# LinearMixer.net
KiCad netlist of a schematic drawn in EAGLE
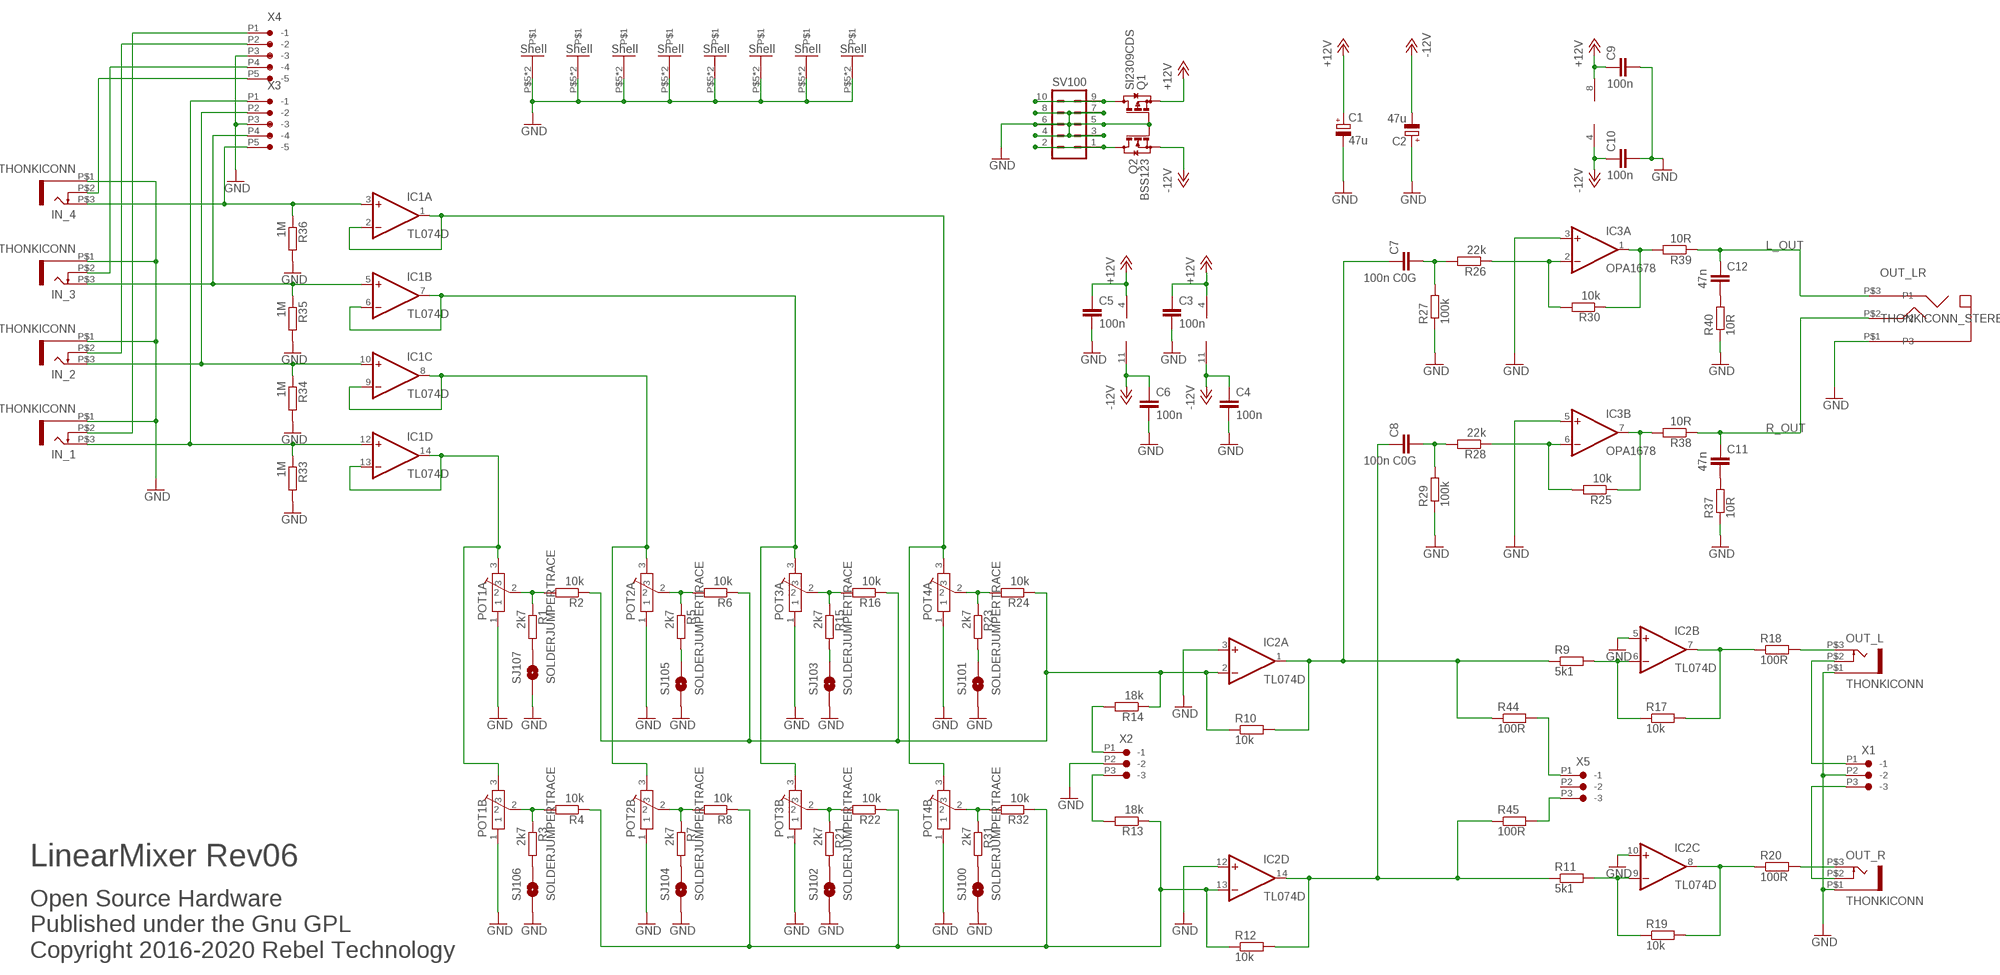
[diagram p0: schematic, sheet 1]

(export (version "E")
  (design (tool "Eeschema 10.0.6"))
  (components
    (comp (ref "C1")
      (value "47u")
      (footprint "eagle-import:153CLV-0505")
      (libsource (lib "eagle-import") (part "CPOL-EU153CLV-0505"))
    )
    (comp (ref "C2")
      (value "47u")
      (footprint "eagle-import:153CLV-0505")
      (libsource (lib "eagle-import") (part "CPOL-EU153CLV-0505"))
    )
    (comp (ref "C3")
      (value "100n")
      (footprint "eagle-import:C0603")
      (libsource (lib "eagle-import") (part "Rebel_15457297_C-EUC0603"))
    )
    (comp (ref "C4")
      (value "100n")
      (footprint "eagle-import:C0603")
      (libsource (lib "eagle-import") (part "Rebel_15457297_C-EUC0603"))
    )
    (comp (ref "C5")
      (value "100n")
      (footprint "eagle-import:C0603")
      (libsource (lib "eagle-import") (part "Rebel_15457297_C-EUC0603"))
    )
    (comp (ref "C6")
      (value "100n")
      (footprint "eagle-import:C0603")
      (libsource (lib "eagle-import") (part "Rebel_15457297_C-EUC0603"))
    )
    (comp (ref "C7")
      (value "100n C0G")
      (footprint "eagle-import:C1210")
      (libsource (lib "eagle-import") (part "C-EUC1210"))
    )
    (comp (ref "C8")
      (value "100n C0G")
      (footprint "eagle-import:C1210")
      (libsource (lib "eagle-import") (part "C-EUC1210"))
    )
    (comp (ref "C9")
      (value "100n")
      (footprint "eagle-import:C0603")
      (libsource (lib "eagle-import") (part "Rebel_15457297_C-EUC0603"))
    )
    (comp (ref "C10")
      (value "100n")
      (footprint "eagle-import:C0603")
      (libsource (lib "eagle-import") (part "Rebel_15457297_C-EUC0603"))
    )
    (comp (ref "C11")
      (value "47n")
      (footprint "eagle-import:C0603")
      (libsource (lib "eagle-import") (part "Rebel_15457297_C-EUC0603"))
    )
    (comp (ref "C12")
      (value "47n")
      (footprint "eagle-import:C0603")
      (libsource (lib "eagle-import") (part "Rebel_15457297_C-EUC0603"))
    )
    (comp (ref "IC1")
      (value "TL074D")
      (footprint "eagle-import:SO14")
      (libsource (lib "eagle-import") (part "TL074D"))
    )
    (comp (ref "IC2")
      (value "TL074D")
      (footprint "eagle-import:SO14")
      (libsource (lib "eagle-import") (part "TL074D"))
    )
    (comp (ref "IC3")
      (value "OPA1678")
      (footprint "eagle-import:SO08")
      (libsource (lib "eagle-import") (part "NE5532D"))
    )
    (comp (ref "IN_1")
      (value "THONKICONN")
      (footprint "eagle-import:THONKICONN")
      (libsource (lib "eagle-import") (part "THONKICONN"))
    )
    (comp (ref "IN_2")
      (value "THONKICONN")
      (footprint "eagle-import:THONKICONN")
      (libsource (lib "eagle-import") (part "THONKICONN"))
    )
    (comp (ref "IN_3")
      (value "THONKICONN")
      (footprint "eagle-import:THONKICONN")
      (libsource (lib "eagle-import") (part "THONKICONN"))
    )
    (comp (ref "IN_4")
      (value "THONKICONN")
      (footprint "eagle-import:THONKICONN")
      (libsource (lib "eagle-import") (part "THONKICONN"))
    )
    (comp (ref "OUT_L")
      (value "THONKICONN")
      (footprint "eagle-import:THONKICONN")
      (libsource (lib "eagle-import") (part "THONKICONN"))
    )
    (comp (ref "OUT_LR")
      (value "THONKICONN_STEREO")
      (footprint "eagle-import:THONKICONN_STEREO")
      (libsource (lib "eagle-import") (part "THONKICONN_STEREO"))
    )
    (comp (ref "OUT_R")
      (value "THONKICONN")
      (footprint "eagle-import:THONKICONN")
      (libsource (lib "eagle-import") (part "THONKICONN"))
    )
    (comp (ref "POT1A")
      (value "POT-ALPS-RK09L1140")
      (footprint "eagle-import:POT-ALPS-RK09L1140")
      (libsource (lib "eagle-import") (part "POT-ALPS-RK09L1140"))
    )
    (comp (ref "POT1B")
      (value "POT-ALPS-RK09L1140")
      (footprint "eagle-import:POT-ALPS-RK09L1140")
      (libsource (lib "eagle-import") (part "POT-ALPS-RK09L1140"))
    )
    (comp (ref "POT2A")
      (value "POT-ALPS-RK09L1140")
      (footprint "eagle-import:POT-ALPS-RK09L1140")
      (libsource (lib "eagle-import") (part "POT-ALPS-RK09L1140"))
    )
    (comp (ref "POT2B")
      (value "POT-ALPS-RK09L1140")
      (footprint "eagle-import:POT-ALPS-RK09L1140")
      (libsource (lib "eagle-import") (part "POT-ALPS-RK09L1140"))
    )
    (comp (ref "POT3A")
      (value "POT-ALPS-RK09L1140")
      (footprint "eagle-import:POT-ALPS-RK09L1140")
      (libsource (lib "eagle-import") (part "POT-ALPS-RK09L1140"))
    )
    (comp (ref "POT3B")
      (value "POT-ALPS-RK09L1140")
      (footprint "eagle-import:POT-ALPS-RK09L1140")
      (libsource (lib "eagle-import") (part "POT-ALPS-RK09L1140"))
    )
    (comp (ref "POT4A")
      (value "POT-ALPS-RK09L1140")
      (footprint "eagle-import:POT-ALPS-RK09L1140")
      (libsource (lib "eagle-import") (part "POT-ALPS-RK09L1140"))
    )
    (comp (ref "POT4B")
      (value "POT-ALPS-RK09L1140")
      (footprint "eagle-import:POT-ALPS-RK09L1140")
      (libsource (lib "eagle-import") (part "POT-ALPS-RK09L1140"))
    )
    (comp (ref "Q1")
      (value "SI2309CDS")
      (footprint "eagle-import:SOT23")
      (libsource (lib "eagle-import") (part "BSS84"))
    )
    (comp (ref "Q2")
      (value "BSS123")
      (footprint "eagle-import:SOT23")
      (libsource (lib "eagle-import") (part "BSS123"))
    )
    (comp (ref "R1")
      (value "2k7")
      (footprint "eagle-import:0603")
      (libsource (lib "eagle-import") (part "Rebel_15457297_R-EU_0603"))
    )
    (comp (ref "R2")
      (value "10k")
      (footprint "eagle-import:0603")
      (libsource (lib "eagle-import") (part "Rebel_15457297_R-EU_0603"))
    )
    (comp (ref "R3")
      (value "2k7")
      (footprint "eagle-import:0603")
      (libsource (lib "eagle-import") (part "Rebel_15457297_R-EU_0603"))
    )
    (comp (ref "R4")
      (value "10k")
      (footprint "eagle-import:0603")
      (libsource (lib "eagle-import") (part "Rebel_15457297_R-EU_0603"))
    )
    (comp (ref "R5")
      (value "2k7")
      (footprint "eagle-import:0603")
      (libsource (lib "eagle-import") (part "Rebel_15457297_R-EU_0603"))
    )
    (comp (ref "R6")
      (value "10k")
      (footprint "eagle-import:0603")
      (libsource (lib "eagle-import") (part "Rebel_15457297_R-EU_0603"))
    )
    (comp (ref "R7")
      (value "2k7")
      (footprint "eagle-import:0603")
      (libsource (lib "eagle-import") (part "Rebel_15457297_R-EU_0603"))
    )
    (comp (ref "R8")
      (value "10k")
      (footprint "eagle-import:0603")
      (libsource (lib "eagle-import") (part "Rebel_15457297_R-EU_0603"))
    )
    (comp (ref "R9")
      (value "5k1")
      (footprint "eagle-import:0603")
      (libsource (lib "eagle-import") (part "Rebel_15457297_R-EU_0603"))
    )
    (comp (ref "R10")
      (value "10k")
      (footprint "eagle-import:0603")
      (libsource (lib "eagle-import") (part "Rebel_15457297_R-EU_0603"))
    )
    (comp (ref "R11")
      (value "5k1")
      (footprint "eagle-import:0603")
      (libsource (lib "eagle-import") (part "Rebel_15457297_R-EU_0603"))
    )
    (comp (ref "R12")
      (value "10k")
      (footprint "eagle-import:0603")
      (libsource (lib "eagle-import") (part "Rebel_15457297_R-EU_0603"))
    )
    (comp (ref "R13")
      (value "18k")
      (footprint "eagle-import:0603")
      (libsource (lib "eagle-import") (part "Rebel_15457297_R-EU_0603"))
    )
    (comp (ref "R14")
      (value "18k")
      (footprint "eagle-import:0603")
      (libsource (lib "eagle-import") (part "Rebel_15457297_R-EU_0603"))
    )
    (comp (ref "R15")
      (value "2k7")
      (footprint "eagle-import:0603")
      (libsource (lib "eagle-import") (part "Rebel_15457297_R-EU_0603"))
    )
    (comp (ref "R16")
      (value "10k")
      (footprint "eagle-import:0603")
      (libsource (lib "eagle-import") (part "Rebel_15457297_R-EU_0603"))
    )
    (comp (ref "R17")
      (value "10k")
      (footprint "eagle-import:0603")
      (libsource (lib "eagle-import") (part "Rebel_15457297_R-EU_0603"))
    )
    (comp (ref "R18")
      (value "100R")
      (footprint "eagle-import:0603")
      (libsource (lib "eagle-import") (part "Rebel_15457297_R-EU_0603"))
    )
    (comp (ref "R19")
      (value "10k")
      (footprint "eagle-import:0603")
      (libsource (lib "eagle-import") (part "Rebel_15457297_R-EU_0603"))
    )
    (comp (ref "R20")
      (value "100R")
      (footprint "eagle-import:0603")
      (libsource (lib "eagle-import") (part "Rebel_15457297_R-EU_0603"))
    )
    (comp (ref "R21")
      (value "2k7")
      (footprint "eagle-import:0603")
      (libsource (lib "eagle-import") (part "Rebel_15457297_R-EU_0603"))
    )
    (comp (ref "R22")
      (value "10k")
      (footprint "eagle-import:0603")
      (libsource (lib "eagle-import") (part "Rebel_15457297_R-EU_0603"))
    )
    (comp (ref "R23")
      (value "2k7")
      (footprint "eagle-import:0603")
      (libsource (lib "eagle-import") (part "Rebel_15457297_R-EU_0603"))
    )
    (comp (ref "R24")
      (value "10k")
      (footprint "eagle-import:0603")
      (libsource (lib "eagle-import") (part "Rebel_15457297_R-EU_0603"))
    )
    (comp (ref "R25")
      (value "10k")
      (footprint "eagle-import:0603")
      (libsource (lib "eagle-import") (part "Rebel_15457297_R-EU_0603"))
    )
    (comp (ref "R26")
      (value "22k")
      (footprint "eagle-import:0603")
      (libsource (lib "eagle-import") (part "Rebel_15457297_R-EU_0603"))
    )
    (comp (ref "R27")
      (value "100k")
      (footprint "eagle-import:0603")
      (libsource (lib "eagle-import") (part "Rebel_15457297_R-EU_0603"))
    )
    (comp (ref "R28")
      (value "22k")
      (footprint "eagle-import:0603")
      (libsource (lib "eagle-import") (part "Rebel_15457297_R-EU_0603"))
    )
    (comp (ref "R29")
      (value "100k")
      (footprint "eagle-import:0603")
      (libsource (lib "eagle-import") (part "Rebel_15457297_R-EU_0603"))
    )
    (comp (ref "R30")
      (value "10k")
      (footprint "eagle-import:0603")
      (libsource (lib "eagle-import") (part "Rebel_15457297_R-EU_0603"))
    )
    (comp (ref "R31")
      (value "2k7")
      (footprint "eagle-import:0603")
      (libsource (lib "eagle-import") (part "Rebel_15457297_R-EU_0603"))
    )
    (comp (ref "R32")
      (value "10k")
      (footprint "eagle-import:0603")
      (libsource (lib "eagle-import") (part "Rebel_15457297_R-EU_0603"))
    )
    (comp (ref "R33")
      (value "1M")
      (footprint "eagle-import:0603")
      (libsource (lib "eagle-import") (part "Rebel_15457297_R-EU_0603"))
    )
    (comp (ref "R34")
      (value "1M")
      (footprint "eagle-import:0603")
      (libsource (lib "eagle-import") (part "Rebel_15457297_R-EU_0603"))
    )
    (comp (ref "R35")
      (value "1M")
      (footprint "eagle-import:0603")
      (libsource (lib "eagle-import") (part "Rebel_15457297_R-EU_0603"))
    )
    (comp (ref "R36")
      (value "1M")
      (footprint "eagle-import:0603")
      (libsource (lib "eagle-import") (part "Rebel_15457297_R-EU_0603"))
    )
    (comp (ref "R37")
      (value "10R")
      (footprint "eagle-import:0603")
      (libsource (lib "eagle-import") (part "Rebel_15457297_R-EU_0603"))
    )
    (comp (ref "R38")
      (value "10R")
      (footprint "eagle-import:0603")
      (libsource (lib "eagle-import") (part "Rebel_15457297_R-EU_0603"))
    )
    (comp (ref "R39")
      (value "10R")
      (footprint "eagle-import:0603")
      (libsource (lib "eagle-import") (part "Rebel_15457297_R-EU_0603"))
    )
    (comp (ref "R40")
      (value "10R")
      (footprint "eagle-import:0603")
      (libsource (lib "eagle-import") (part "Rebel_15457297_R-EU_0603"))
    )
    (comp (ref "R44")
      (value "100R")
      (footprint "eagle-import:0603")
      (libsource (lib "eagle-import") (part "R-EU_0603"))
    )
    (comp (ref "R45")
      (value "100R")
      (footprint "eagle-import:0603")
      (libsource (lib "eagle-import") (part "R-EU_0603"))
    )
    (comp (ref "SJ100")
      (value "SOLDERJUMPERTRACE")
      (footprint "eagle-import:SJ_2S-TRACE")
      (libsource (lib "eagle-import") (part "SOLDERJUMPERTRACE"))
    )
    (comp (ref "SJ101")
      (value "SOLDERJUMPERTRACE")
      (footprint "eagle-import:SJ_2S-TRACE")
      (libsource (lib "eagle-import") (part "SOLDERJUMPERTRACE"))
    )
    (comp (ref "SJ102")
      (value "SOLDERJUMPERTRACE")
      (footprint "eagle-import:SJ_2S-TRACE")
      (libsource (lib "eagle-import") (part "SOLDERJUMPERTRACE"))
    )
    (comp (ref "SJ103")
      (value "SOLDERJUMPERTRACE")
      (footprint "eagle-import:SJ_2S-TRACE")
      (libsource (lib "eagle-import") (part "SOLDERJUMPERTRACE"))
    )
    (comp (ref "SJ104")
      (value "SOLDERJUMPERTRACE")
      (footprint "eagle-import:SJ_2S-TRACE")
      (libsource (lib "eagle-import") (part "SOLDERJUMPERTRACE"))
    )
    (comp (ref "SJ105")
      (value "SOLDERJUMPERTRACE")
      (footprint "eagle-import:SJ_2S-TRACE")
      (libsource (lib "eagle-import") (part "SOLDERJUMPERTRACE"))
    )
    (comp (ref "SJ106")
      (value "SOLDERJUMPERTRACE")
      (footprint "eagle-import:SJ_2S-TRACE")
      (libsource (lib "eagle-import") (part "SOLDERJUMPERTRACE"))
    )
    (comp (ref "SJ107")
      (value "SOLDERJUMPERTRACE")
      (footprint "eagle-import:SJ_2S-TRACE")
      (libsource (lib "eagle-import") (part "SOLDERJUMPERTRACE"))
    )
    (comp (ref "SV100")
      (value "MA05-2")
      (footprint "eagle-import:MA05-2")
      (libsource (lib "eagle-import") (part "MA05-2"))
    )
    (comp (ref "X1")
      (value "CON-JST_PH_3W")
      (footprint "eagle-import:CON-JST_PH_3W")
      (libsource (lib "eagle-import") (part "CON-JST_PH_3W"))
    )
    (comp (ref "X2")
      (value "CON-JST_PH_3W")
      (footprint "eagle-import:CON-JST_PH_3W")
      (libsource (lib "eagle-import") (part "CON-JST_PH_3W"))
    )
    (comp (ref "X3")
      (value "CON-JST_PH_5W")
      (footprint "eagle-import:CON-JST_PH_5W")
      (libsource (lib "eagle-import") (part "CON-JST_PH_5W"))
    )
    (comp (ref "X4")
      (value "CON-JST_PH_5W")
      (footprint "eagle-import:CON-JST_PH_5W")
      (libsource (lib "eagle-import") (part "CON-JST_PH_5W"))
    )
    (comp (ref "X5")
      (value "CON-JST_PH_3W")
      (footprint "eagle-import:CON-JST_PH_3W")
      (libsource (lib "eagle-import") (part "CON-JST_PH_3W"))
    )
  )
  (nets
    (net (code "1") (name "+12V") (class "Default")
      (node (ref "C1") (pin "+") (pinfunction "+_+") (pintype "passive"))
      (node (ref "C3") (pin "1") (pinfunction "1_1") (pintype "passive"))
      (node (ref "C5") (pin "1") (pinfunction "1_1") (pintype "passive"))
      (node (ref "C9") (pin "1") (pinfunction "1_1") (pintype "passive"))
      (node (ref "IC1") (pin "4") (pinfunction "V+_4") (pintype "power_in"))
      (node (ref "IC2") (pin "4") (pinfunction "V+_4") (pintype "power_in"))
      (node (ref "IC3") (pin "8") (pinfunction "V+_8") (pintype "power_in"))
      (node (ref "Q1") (pin "2") (pinfunction "S_2") (pintype "passive"))
    )
    (net (code "2") (name "-12V") (class "Default")
      (node (ref "C10") (pin "1") (pinfunction "1_1") (pintype "passive"))
      (node (ref "C2") (pin "-") (pinfunction "-_-") (pintype "passive"))
      (node (ref "C4") (pin "1") (pinfunction "1_1") (pintype "passive"))
      (node (ref "C6") (pin "1") (pinfunction "1_1") (pintype "passive"))
      (node (ref "IC1") (pin "11") (pinfunction "V-_11") (pintype "power_in"))
      (node (ref "IC2") (pin "11") (pinfunction "V-_11") (pintype "power_in"))
      (node (ref "IC3") (pin "4") (pinfunction "V-_4") (pintype "power_in"))
      (node (ref "Q2") (pin "2") (pinfunction "S_2") (pintype "passive"))
    )
    (net (code "3") (name "/L_OUT") (class "Default")
      (node (ref "C12") (pin "1") (pinfunction "1_1") (pintype "passive"))
      (node (ref "OUT_LR") (pin "P$3") (pinfunction "P1_P$3") (pintype "bidirectional"))
      (node (ref "R39") (pin "1") (pinfunction "1_1") (pintype "passive"))
    )
    (net (code "4") (name "/R_OUT") (class "Default")
      (node (ref "C11") (pin "1") (pinfunction "1_1") (pintype "passive"))
      (node (ref "OUT_LR") (pin "P$2") (pinfunction "P2_P$2") (pintype "bidirectional"))
      (node (ref "R38") (pin "1") (pinfunction "1_1") (pintype "passive"))
    )
    (net (code "5") (name "GND") (class "Default")
      (node (ref "C1") (pin "-") (pinfunction "-_-") (pintype "passive"))
      (node (ref "C10") (pin "2") (pinfunction "2_2") (pintype "passive"))
      (node (ref "C2") (pin "+") (pinfunction "+_+") (pintype "passive"))
      (node (ref "C3") (pin "2") (pinfunction "2_2") (pintype "passive"))
      (node (ref "C4") (pin "2") (pinfunction "2_2") (pintype "passive"))
      (node (ref "C5") (pin "2") (pinfunction "2_2") (pintype "passive"))
      (node (ref "C6") (pin "2") (pinfunction "2_2") (pintype "passive"))
      (node (ref "C9") (pin "2") (pinfunction "2_2") (pintype "passive"))
      (node (ref "IC2") (pin "10") (pinfunction "+IN_10") (pintype "input"))
      (node (ref "IC2") (pin "12") (pinfunction "+IN_12") (pintype "input"))
      (node (ref "IC2") (pin "3") (pinfunction "+IN_3") (pintype "input"))
      (node (ref "IC2") (pin "5") (pinfunction "+IN_5") (pintype "input"))
      (node (ref "IC3") (pin "3") (pinfunction "+IN_3") (pintype "input"))
      (node (ref "IC3") (pin "5") (pinfunction "+IN_5") (pintype "input"))
      (node (ref "IN_1") (pin "P$1") (pinfunction "5_P$1") (pintype "passive"))
      (node (ref "IN_2") (pin "P$1") (pinfunction "5_P$1") (pintype "passive"))
      (node (ref "IN_3") (pin "P$1") (pinfunction "5_P$1") (pintype "passive"))
      (node (ref "IN_4") (pin "P$1") (pinfunction "5_P$1") (pintype "passive"))
      (node (ref "OUT_L") (pin "P$1") (pinfunction "5_P$1") (pintype "passive"))
      (node (ref "OUT_LR") (pin "P$1") (pinfunction "P3_P$1") (pintype "bidirectional"))
      (node (ref "OUT_R") (pin "P$1") (pinfunction "5_P$1") (pintype "passive"))
      (node (ref "POT1A") (pin "1") (pinfunction "1_1") (pintype "bidirectional"))
      (node (ref "POT1A") (pin "P$5") (pinfunction "P$1_P$5") (pintype "bidirectional"))
      (node (ref "POT1A") (pin "P$6") (pinfunction "P$1_P$6") (pintype "bidirectional"))
      (node (ref "POT1B") (pin "1") (pinfunction "1_1") (pintype "bidirectional"))
      (node (ref "POT1B") (pin "P$5") (pinfunction "P$1_P$5") (pintype "bidirectional"))
      (node (ref "POT1B") (pin "P$6") (pinfunction "P$1_P$6") (pintype "bidirectional"))
      (node (ref "POT2A") (pin "1") (pinfunction "1_1") (pintype "bidirectional"))
      (node (ref "POT2A") (pin "P$5") (pinfunction "P$1_P$5") (pintype "bidirectional"))
      (node (ref "POT2A") (pin "P$6") (pinfunction "P$1_P$6") (pintype "bidirectional"))
      (node (ref "POT2B") (pin "1") (pinfunction "1_1") (pintype "bidirectional"))
      (node (ref "POT2B") (pin "P$5") (pinfunction "P$1_P$5") (pintype "bidirectional"))
      (node (ref "POT2B") (pin "P$6") (pinfunction "P$1_P$6") (pintype "bidirectional"))
      (node (ref "POT3A") (pin "1") (pinfunction "1_1") (pintype "bidirectional"))
      (node (ref "POT3A") (pin "P$5") (pinfunction "P$1_P$5") (pintype "bidirectional"))
      (node (ref "POT3A") (pin "P$6") (pinfunction "P$1_P$6") (pintype "bidirectional"))
      (node (ref "POT3B") (pin "1") (pinfunction "1_1") (pintype "bidirectional"))
      (node (ref "POT3B") (pin "P$5") (pinfunction "P$1_P$5") (pintype "bidirectional"))
      (node (ref "POT3B") (pin "P$6") (pinfunction "P$1_P$6") (pintype "bidirectional"))
      (node (ref "POT4A") (pin "1") (pinfunction "1_1") (pintype "bidirectional"))
      (node (ref "POT4A") (pin "P$5") (pinfunction "P$1_P$5") (pintype "bidirectional"))
      (node (ref "POT4A") (pin "P$6") (pinfunction "P$1_P$6") (pintype "bidirectional"))
      (node (ref "POT4B") (pin "1") (pinfunction "1_1") (pintype "bidirectional"))
      (node (ref "POT4B") (pin "P$5") (pinfunction "P$1_P$5") (pintype "bidirectional"))
      (node (ref "POT4B") (pin "P$6") (pinfunction "P$1_P$6") (pintype "bidirectional"))
      (node (ref "Q1") (pin "1") (pinfunction "G_1") (pintype "passive"))
      (node (ref "Q2") (pin "1") (pinfunction "G_1") (pintype "passive"))
      (node (ref "R27") (pin "1") (pinfunction "1_1") (pintype "passive"))
      (node (ref "R29") (pin "1") (pinfunction "1_1") (pintype "passive"))
      (node (ref "R33") (pin "2") (pinfunction "2_2") (pintype "passive"))
      (node (ref "R34") (pin "2") (pinfunction "2_2") (pintype "passive"))
      (node (ref "R35") (pin "2") (pinfunction "2_2") (pintype "passive"))
      (node (ref "R36") (pin "2") (pinfunction "2_2") (pintype "passive"))
      (node (ref "R37") (pin "1") (pinfunction "1_1") (pintype "passive"))
      (node (ref "R40") (pin "1") (pinfunction "1_1") (pintype "passive"))
      (node (ref "SJ100") (pin "1") (pinfunction "1_1") (pintype "passive"))
      (node (ref "SJ101") (pin "1") (pinfunction "1_1") (pintype "passive"))
      (node (ref "SJ102") (pin "1") (pinfunction "1_1") (pintype "passive"))
      (node (ref "SJ103") (pin "1") (pinfunction "1_1") (pintype "passive"))
      (node (ref "SJ104") (pin "1") (pinfunction "1_1") (pintype "passive"))
      (node (ref "SJ105") (pin "1") (pinfunction "1_1") (pintype "passive"))
      (node (ref "SJ106") (pin "1") (pinfunction "1_1") (pintype "passive"))
      (node (ref "SJ107") (pin "1") (pinfunction "1_1") (pintype "passive"))
      (node (ref "SV100") (pin "3") (pinfunction "3_3") (pintype "passive"))
      (node (ref "SV100") (pin "4") (pinfunction "4_4") (pintype "passive"))
      (node (ref "SV100") (pin "5") (pinfunction "5_5") (pintype "passive"))
      (node (ref "SV100") (pin "6") (pinfunction "6_6") (pintype "passive"))
      (node (ref "SV100") (pin "7") (pinfunction "7_7") (pintype "passive"))
      (node (ref "SV100") (pin "8") (pinfunction "8_8") (pintype "passive"))
      (node (ref "X1") (pin "P2") (pinfunction "-2_P2") (pintype "bidirectional"))
      (node (ref "X2") (pin "P2") (pinfunction "-2_P2") (pintype "bidirectional"))
      (node (ref "X3") (pin "P3") (pinfunction "-3_P3") (pintype "bidirectional"))
      (node (ref "X4") (pin "P3") (pinfunction "-3_P3") (pintype "bidirectional"))
    )
    (net (code "6") (name "Net-(C7-Pad2)") (class "Default")
      (node (ref "C7") (pin "2") (pinfunction "2_2") (pintype "passive"))
      (node (ref "R26") (pin "2") (pinfunction "2_2") (pintype "passive"))
      (node (ref "R27") (pin "2") (pinfunction "2_2") (pintype "passive"))
    )
    (net (code "7") (name "Net-(C8-Pad2)") (class "Default")
      (node (ref "C8") (pin "2") (pinfunction "2_2") (pintype "passive"))
      (node (ref "R28") (pin "2") (pinfunction "2_2") (pintype "passive"))
      (node (ref "R29") (pin "2") (pinfunction "2_2") (pintype "passive"))
    )
    (net (code "8") (name "Net-(C11-Pad2)") (class "Default")
      (node (ref "C11") (pin "2") (pinfunction "2_2") (pintype "passive"))
      (node (ref "R37") (pin "2") (pinfunction "2_2") (pintype "passive"))
    )
    (net (code "9") (name "Net-(C12-Pad2)") (class "Default")
      (node (ref "C12") (pin "2") (pinfunction "2_2") (pintype "passive"))
      (node (ref "R40") (pin "2") (pinfunction "2_2") (pintype "passive"))
    )
    (net (code "10") (name "Net-(IC1A-+IN)") (class "Default")
      (node (ref "IC1") (pin "3") (pinfunction "+IN_3") (pintype "input"))
      (node (ref "IN_4") (pin "P$3") (pinfunction "3_P$3") (pintype "passive"))
      (node (ref "R36") (pin "1") (pinfunction "1_1") (pintype "passive"))
      (node (ref "X3") (pin "P5") (pinfunction "-5_P5") (pintype "bidirectional"))
    )
    (net (code "11") (name "Net-(IC1A--IN)") (class "Default")
      (node (ref "IC1") (pin "1") (pinfunction "OUT_1") (pintype "output"))
      (node (ref "IC1") (pin "2") (pinfunction "-IN_2") (pintype "input"))
      (node (ref "POT4A") (pin "3") (pinfunction "3_3") (pintype "bidirectional"))
      (node (ref "POT4B") (pin "3") (pinfunction "3_3") (pintype "bidirectional"))
    )
    (net (code "12") (name "Net-(IC1B-+IN)") (class "Default")
      (node (ref "IC1") (pin "5") (pinfunction "+IN_5") (pintype "input"))
      (node (ref "IN_3") (pin "P$3") (pinfunction "3_P$3") (pintype "passive"))
      (node (ref "R35") (pin "1") (pinfunction "1_1") (pintype "passive"))
      (node (ref "X3") (pin "P4") (pinfunction "-4_P4") (pintype "bidirectional"))
    )
    (net (code "13") (name "Net-(IC1B--IN)") (class "Default")
      (node (ref "IC1") (pin "6") (pinfunction "-IN_6") (pintype "input"))
      (node (ref "IC1") (pin "7") (pinfunction "OUT_7") (pintype "output"))
      (node (ref "POT3A") (pin "3") (pinfunction "3_3") (pintype "bidirectional"))
      (node (ref "POT3B") (pin "3") (pinfunction "3_3") (pintype "bidirectional"))
    )
    (net (code "14") (name "Net-(IC1C-+IN)") (class "Default")
      (node (ref "IC1") (pin "10") (pinfunction "+IN_10") (pintype "input"))
      (node (ref "IN_2") (pin "P$3") (pinfunction "3_P$3") (pintype "passive"))
      (node (ref "R34") (pin "1") (pinfunction "1_1") (pintype "passive"))
      (node (ref "X3") (pin "P2") (pinfunction "-2_P2") (pintype "bidirectional"))
    )
    (net (code "15") (name "Net-(IC1C--IN)") (class "Default")
      (node (ref "IC1") (pin "8") (pinfunction "OUT_8") (pintype "output"))
      (node (ref "IC1") (pin "9") (pinfunction "-IN_9") (pintype "input"))
      (node (ref "POT2A") (pin "3") (pinfunction "3_3") (pintype "bidirectional"))
      (node (ref "POT2B") (pin "3") (pinfunction "3_3") (pintype "bidirectional"))
    )
    (net (code "16") (name "Net-(IC1D-+IN)") (class "Default")
      (node (ref "IC1") (pin "12") (pinfunction "+IN_12") (pintype "input"))
      (node (ref "IN_1") (pin "P$3") (pinfunction "3_P$3") (pintype "passive"))
      (node (ref "R33") (pin "1") (pinfunction "1_1") (pintype "passive"))
      (node (ref "X3") (pin "P1") (pinfunction "-1_P1") (pintype "bidirectional"))
    )
    (net (code "17") (name "Net-(IC1D--IN)") (class "Default")
      (node (ref "IC1") (pin "13") (pinfunction "-IN_13") (pintype "input"))
      (node (ref "IC1") (pin "14") (pinfunction "OUT_14") (pintype "output"))
      (node (ref "POT1A") (pin "3") (pinfunction "3_3") (pintype "bidirectional"))
      (node (ref "POT1B") (pin "3") (pinfunction "3_3") (pintype "bidirectional"))
    )
    (net (code "18") (name "Net-(IC2A--IN)") (class "Default")
      (node (ref "IC2") (pin "2") (pinfunction "-IN_2") (pintype "input"))
      (node (ref "R10") (pin "1") (pinfunction "1_1") (pintype "passive"))
      (node (ref "R14") (pin "1") (pinfunction "1_1") (pintype "passive"))
      (node (ref "R16") (pin "1") (pinfunction "1_1") (pintype "passive"))
      (node (ref "R2") (pin "1") (pinfunction "1_1") (pintype "passive"))
      (node (ref "R24") (pin "1") (pinfunction "1_1") (pintype "passive"))
      (node (ref "R6") (pin "1") (pinfunction "1_1") (pintype "passive"))
    )
    (net (code "19") (name "Net-(IC2A-OUT)") (class "Default")
      (node (ref "C7") (pin "1") (pinfunction "1_1") (pintype "passive"))
      (node (ref "IC2") (pin "1") (pinfunction "OUT_1") (pintype "output"))
      (node (ref "R10") (pin "2") (pinfunction "2_2") (pintype "passive"))
      (node (ref "R44") (pin "1") (pinfunction "1_1") (pintype "passive"))
      (node (ref "R9") (pin "1") (pinfunction "1_1") (pintype "passive"))
    )
    (net (code "20") (name "Net-(IC2B--IN)") (class "Default")
      (node (ref "IC2") (pin "6") (pinfunction "-IN_6") (pintype "input"))
      (node (ref "R17") (pin "1") (pinfunction "1_1") (pintype "passive"))
      (node (ref "R9") (pin "2") (pinfunction "2_2") (pintype "passive"))
    )
    (net (code "21") (name "Net-(IC2B-OUT)") (class "Default")
      (node (ref "IC2") (pin "7") (pinfunction "OUT_7") (pintype "output"))
      (node (ref "R17") (pin "2") (pinfunction "2_2") (pintype "passive"))
      (node (ref "R18") (pin "1") (pinfunction "1_1") (pintype "passive"))
    )
    (net (code "22") (name "Net-(IC2C--IN)") (class "Default")
      (node (ref "IC2") (pin "9") (pinfunction "-IN_9") (pintype "input"))
      (node (ref "R11") (pin "2") (pinfunction "2_2") (pintype "passive"))
      (node (ref "R19") (pin "1") (pinfunction "1_1") (pintype "passive"))
    )
    (net (code "23") (name "Net-(IC2C-OUT)") (class "Default")
      (node (ref "IC2") (pin "8") (pinfunction "OUT_8") (pintype "output"))
      (node (ref "R19") (pin "2") (pinfunction "2_2") (pintype "passive"))
      (node (ref "R20") (pin "1") (pinfunction "1_1") (pintype "passive"))
    )
    (net (code "24") (name "Net-(IC2D--IN)") (class "Default")
      (node (ref "IC2") (pin "13") (pinfunction "-IN_13") (pintype "input"))
      (node (ref "R12") (pin "1") (pinfunction "1_1") (pintype "passive"))
      (node (ref "R13") (pin "1") (pinfunction "1_1") (pintype "passive"))
      (node (ref "R22") (pin "1") (pinfunction "1_1") (pintype "passive"))
      (node (ref "R32") (pin "1") (pinfunction "1_1") (pintype "passive"))
      (node (ref "R4") (pin "1") (pinfunction "1_1") (pintype "passive"))
      (node (ref "R8") (pin "1") (pinfunction "1_1") (pintype "passive"))
    )
    (net (code "25") (name "Net-(IC2D-OUT)") (class "Default")
      (node (ref "C8") (pin "1") (pinfunction "1_1") (pintype "passive"))
      (node (ref "IC2") (pin "14") (pinfunction "OUT_14") (pintype "output"))
      (node (ref "R11") (pin "1") (pinfunction "1_1") (pintype "passive"))
      (node (ref "R12") (pin "2") (pinfunction "2_2") (pintype "passive"))
      (node (ref "R45") (pin "1") (pinfunction "1_1") (pintype "passive"))
    )
    (net (code "26") (name "Net-(IC3A--IN)") (class "Default")
      (node (ref "IC3") (pin "2") (pinfunction "-IN_2") (pintype "input"))
      (node (ref "R26") (pin "1") (pinfunction "1_1") (pintype "passive"))
      (node (ref "R30") (pin "2") (pinfunction "2_2") (pintype "passive"))
    )
    (net (code "27") (name "Net-(IC3A-OUT)") (class "Default")
      (node (ref "IC3") (pin "1") (pinfunction "OUT_1") (pintype "output"))
      (node (ref "R30") (pin "1") (pinfunction "1_1") (pintype "passive"))
      (node (ref "R39") (pin "2") (pinfunction "2_2") (pintype "passive"))
    )
    (net (code "28") (name "Net-(IC3B--IN)") (class "Default")
      (node (ref "IC3") (pin "6") (pinfunction "-IN_6") (pintype "input"))
      (node (ref "R25") (pin "2") (pinfunction "2_2") (pintype "passive"))
      (node (ref "R28") (pin "1") (pinfunction "1_1") (pintype "passive"))
    )
    (net (code "29") (name "Net-(IC3B-OUT)") (class "Default")
      (node (ref "IC3") (pin "7") (pinfunction "OUT_7") (pintype "output"))
      (node (ref "R25") (pin "1") (pinfunction "1_1") (pintype "passive"))
      (node (ref "R38") (pin "2") (pinfunction "2_2") (pintype "passive"))
    )
    (net (code "30") (name "Net-(IN_1-4)") (class "Default")
      (node (ref "IN_1") (pin "P$2") (pinfunction "4_P$2") (pintype "passive"))
      (node (ref "X4") (pin "P1") (pinfunction "-1_P1") (pintype "bidirectional"))
    )
    (net (code "31") (name "Net-(IN_2-4)") (class "Default")
      (node (ref "IN_2") (pin "P$2") (pinfunction "4_P$2") (pintype "passive"))
      (node (ref "X4") (pin "P2") (pinfunction "-2_P2") (pintype "bidirectional"))
    )
    (net (code "32") (name "Net-(IN_3-4)") (class "Default")
      (node (ref "IN_3") (pin "P$2") (pinfunction "4_P$2") (pintype "passive"))
      (node (ref "X4") (pin "P4") (pinfunction "-4_P4") (pintype "bidirectional"))
    )
    (net (code "33") (name "Net-(IN_4-4)") (class "Default")
      (node (ref "IN_4") (pin "P$2") (pinfunction "4_P$2") (pintype "passive"))
      (node (ref "X4") (pin "P5") (pinfunction "-5_P5") (pintype "bidirectional"))
    )
    (net (code "34") (name "Net-(OUT_L-3)") (class "Default")
      (node (ref "OUT_L") (pin "P$3") (pinfunction "3_P$3") (pintype "passive"))
      (node (ref "R18") (pin "2") (pinfunction "2_2") (pintype "passive"))
    )
    (net (code "35") (name "Net-(OUT_L-4)") (class "Default")
      (node (ref "OUT_L") (pin "P$2") (pinfunction "4_P$2") (pintype "passive"))
      (node (ref "X1") (pin "P1") (pinfunction "-1_P1") (pintype "bidirectional"))
    )
    (net (code "36") (name "Net-(OUT_R-3)") (class "Default")
      (node (ref "OUT_R") (pin "P$3") (pinfunction "3_P$3") (pintype "passive"))
      (node (ref "R20") (pin "2") (pinfunction "2_2") (pintype "passive"))
    )
    (net (code "37") (name "Net-(OUT_R-4)") (class "Default")
      (node (ref "OUT_R") (pin "P$2") (pinfunction "4_P$2") (pintype "passive"))
      (node (ref "X1") (pin "P3") (pinfunction "-3_P3") (pintype "bidirectional"))
    )
    (net (code "38") (name "Net-(POT1A-Pad2)") (class "Default")
      (node (ref "POT1A") (pin "2") (pinfunction "2_2") (pintype "bidirectional"))
      (node (ref "R1") (pin "1") (pinfunction "1_1") (pintype "passive"))
      (node (ref "R2") (pin "2") (pinfunction "2_2") (pintype "passive"))
    )
    (net (code "39") (name "Net-(POT1B-Pad2)") (class "Default")
      (node (ref "POT1B") (pin "2") (pinfunction "2_2") (pintype "bidirectional"))
      (node (ref "R3") (pin "1") (pinfunction "1_1") (pintype "passive"))
      (node (ref "R4") (pin "2") (pinfunction "2_2") (pintype "passive"))
    )
    (net (code "40") (name "Net-(POT2A-Pad2)") (class "Default")
      (node (ref "POT2A") (pin "2") (pinfunction "2_2") (pintype "bidirectional"))
      (node (ref "R5") (pin "1") (pinfunction "1_1") (pintype "passive"))
      (node (ref "R6") (pin "2") (pinfunction "2_2") (pintype "passive"))
    )
    (net (code "41") (name "Net-(POT2B-Pad2)") (class "Default")
      (node (ref "POT2B") (pin "2") (pinfunction "2_2") (pintype "bidirectional"))
      (node (ref "R7") (pin "1") (pinfunction "1_1") (pintype "passive"))
      (node (ref "R8") (pin "2") (pinfunction "2_2") (pintype "passive"))
    )
    (net (code "42") (name "Net-(POT3A-Pad2)") (class "Default")
      (node (ref "POT3A") (pin "2") (pinfunction "2_2") (pintype "bidirectional"))
      (node (ref "R15") (pin "1") (pinfunction "1_1") (pintype "passive"))
      (node (ref "R16") (pin "2") (pinfunction "2_2") (pintype "passive"))
    )
    (net (code "43") (name "Net-(POT3B-Pad2)") (class "Default")
      (node (ref "POT3B") (pin "2") (pinfunction "2_2") (pintype "bidirectional"))
      (node (ref "R21") (pin "1") (pinfunction "1_1") (pintype "passive"))
      (node (ref "R22") (pin "2") (pinfunction "2_2") (pintype "passive"))
    )
    (net (code "44") (name "Net-(POT4A-Pad2)") (class "Default")
      (node (ref "POT4A") (pin "2") (pinfunction "2_2") (pintype "bidirectional"))
      (node (ref "R23") (pin "1") (pinfunction "1_1") (pintype "passive"))
      (node (ref "R24") (pin "2") (pinfunction "2_2") (pintype "passive"))
    )
    (net (code "45") (name "Net-(POT4B-Pad2)") (class "Default")
      (node (ref "POT4B") (pin "2") (pinfunction "2_2") (pintype "bidirectional"))
      (node (ref "R31") (pin "1") (pinfunction "1_1") (pintype "passive"))
      (node (ref "R32") (pin "2") (pinfunction "2_2") (pintype "passive"))
    )
    (net (code "46") (name "Net-(Q1-D)") (class "Default")
      (node (ref "Q1") (pin "3") (pinfunction "D_3") (pintype "passive"))
      (node (ref "SV100") (pin "10") (pinfunction "10_10") (pintype "passive"))
      (node (ref "SV100") (pin "9") (pinfunction "9_9") (pintype "passive"))
    )
    (net (code "47") (name "Net-(Q2-D)") (class "Default")
      (node (ref "Q2") (pin "3") (pinfunction "D_3") (pintype "passive"))
      (node (ref "SV100") (pin "1") (pinfunction "1_1") (pintype "passive"))
      (node (ref "SV100") (pin "2") (pinfunction "2_2") (pintype "passive"))
    )
    (net (code "48") (name "Net-(R1-Pad2)") (class "Default")
      (node (ref "R1") (pin "2") (pinfunction "2_2") (pintype "passive"))
      (node (ref "SJ107") (pin "2") (pinfunction "2_2") (pintype "passive"))
    )
    (net (code "49") (name "Net-(R3-Pad2)") (class "Default")
      (node (ref "R3") (pin "2") (pinfunction "2_2") (pintype "passive"))
      (node (ref "SJ106") (pin "2") (pinfunction "2_2") (pintype "passive"))
    )
    (net (code "50") (name "Net-(R5-Pad2)") (class "Default")
      (node (ref "R5") (pin "2") (pinfunction "2_2") (pintype "passive"))
      (node (ref "SJ105") (pin "2") (pinfunction "2_2") (pintype "passive"))
    )
    (net (code "51") (name "Net-(R7-Pad2)") (class "Default")
      (node (ref "R7") (pin "2") (pinfunction "2_2") (pintype "passive"))
      (node (ref "SJ104") (pin "2") (pinfunction "2_2") (pintype "passive"))
    )
    (net (code "52") (name "Net-(R15-Pad2)") (class "Default")
      (node (ref "R15") (pin "2") (pinfunction "2_2") (pintype "passive"))
      (node (ref "SJ103") (pin "2") (pinfunction "2_2") (pintype "passive"))
    )
    (net (code "53") (name "Net-(R21-Pad2)") (class "Default")
      (node (ref "R21") (pin "2") (pinfunction "2_2") (pintype "passive"))
      (node (ref "SJ102") (pin "2") (pinfunction "2_2") (pintype "passive"))
    )
    (net (code "54") (name "Net-(R23-Pad2)") (class "Default")
      (node (ref "R23") (pin "2") (pinfunction "2_2") (pintype "passive"))
      (node (ref "SJ101") (pin "2") (pinfunction "2_2") (pintype "passive"))
    )
    (net (code "55") (name "Net-(R31-Pad2)") (class "Default")
      (node (ref "R31") (pin "2") (pinfunction "2_2") (pintype "passive"))
      (node (ref "SJ100") (pin "2") (pinfunction "2_2") (pintype "passive"))
    )
    (net (code "56") (name "Net-(X2--1)") (class "Default")
      (node (ref "R14") (pin "2") (pinfunction "2_2") (pintype "passive"))
      (node (ref "X2") (pin "P1") (pinfunction "-1_P1") (pintype "bidirectional"))
    )
    (net (code "57") (name "Net-(X2--3)") (class "Default")
      (node (ref "R13") (pin "2") (pinfunction "2_2") (pintype "passive"))
      (node (ref "X2") (pin "P3") (pinfunction "-3_P3") (pintype "bidirectional"))
    )
    (net (code "58") (name "Net-(X5--1)") (class "Default")
      (node (ref "R44") (pin "2") (pinfunction "2_2") (pintype "passive"))
      (node (ref "X5") (pin "P1") (pinfunction "-1_P1") (pintype "bidirectional"))
    )
    (net (code "59") (name "Net-(X5--3)") (class "Default")
      (node (ref "R45") (pin "2") (pinfunction "2_2") (pintype "passive"))
      (node (ref "X5") (pin "P3") (pinfunction "-3_P3") (pintype "bidirectional"))
    )
    (net (code "60") (name "unconnected-(X5--2-PadP2)") (class "Default")
      (node (ref "X5") (pin "P2") (pinfunction "-2_P2") (pintype "bidirectional"))
    )
  )
)
